# vario.net
KiCad netlist of a schematic drawn in EAGLE
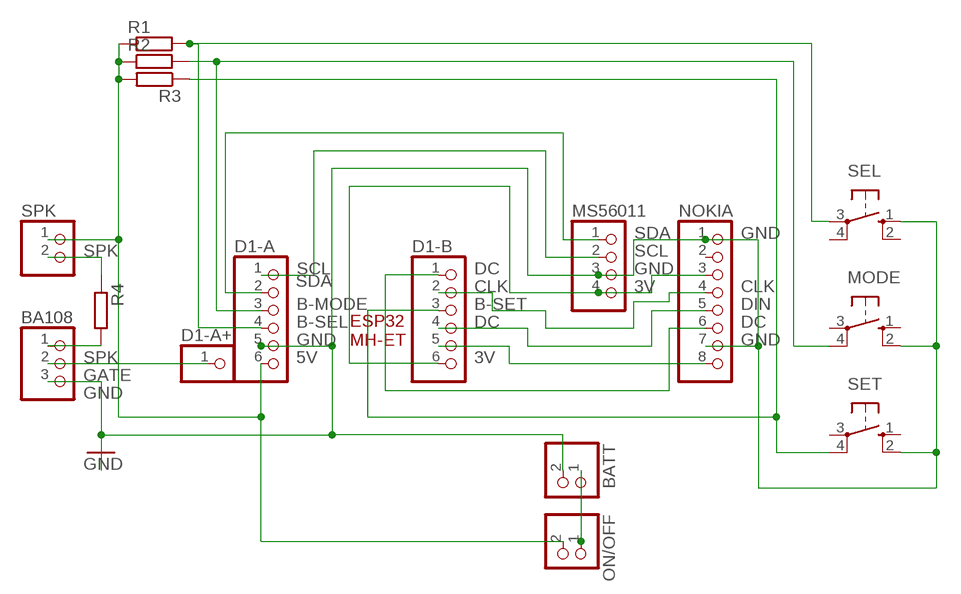
[diagram p0: schematic, sheet 1]

(export (version "E")
  (design (tool "Eeschema 10.0.6"))
  (components
    (comp (ref "BA108")
      (value "PINHD-1X3")
      (footprint "eagle-import:1X03")
      (libsource (lib "eagle-import") (part "PINHD-1X3"))
    )
    (comp (ref "BATT")
      (value "PINHD-1X2")
      (footprint "eagle-import:1X02")
      (libsource (lib "eagle-import") (part "PINHD-1X2"))
    )
    (comp (ref "D1-A")
      (value "PINHD-1X6")
      (footprint "eagle-import:1X06")
      (libsource (lib "eagle-import") (part "PINHD-1X6"))
    )
    (comp (ref "D1-A+")
      (value "PINHD-1X1")
      (footprint "eagle-import:1X01")
      (libsource (lib "eagle-import") (part "PINHD-1X1"))
    )
    (comp (ref "D1-B")
      (value "PINHD-1X6")
      (footprint "eagle-import:1X06")
      (libsource (lib "eagle-import") (part "PINHD-1X6"))
    )
    (comp (ref "MODE")
      (value "10-XX")
      (footprint "eagle-import:B3F-10XX")
      (fields (field (name "MPN") "B3F-1000"))
      (libsource (lib "eagle-import") (part "10-XX"))
    )
    (comp (ref "MS56011")
      (value "PINHD-1X4")
      (footprint "eagle-import:1X04")
      (libsource (lib "eagle-import") (part "PINHD-1X4"))
    )
    (comp (ref "NOKIA")
      (value "PINHD-1X8")
      (footprint "eagle-import:1X08")
      (libsource (lib "eagle-import") (part "PINHD-1X8"))
    )
    (comp (ref "ON/OFF")
      (value "PINHD-1X2")
      (footprint "eagle-import:1X02")
      (libsource (lib "eagle-import") (part "PINHD-1X2"))
    )
    (comp (ref "R1")
      (value "R-EU_0207/10")
      (footprint "eagle-import:0207_10")
      (libsource (lib "eagle-import") (part "R-EU_0207/10"))
    )
    (comp (ref "R2")
      (value "R-EU_0207/10")
      (footprint "eagle-import:0207_10")
      (libsource (lib "eagle-import") (part "R-EU_0207/10"))
    )
    (comp (ref "R3")
      (value "R-EU_0207/10")
      (footprint "eagle-import:0207_10")
      (libsource (lib "eagle-import") (part "R-EU_0207/10"))
    )
    (comp (ref "R4")
      (value "R-EU_0207/10")
      (footprint "eagle-import:0207_10")
      (libsource (lib "eagle-import") (part "R-EU_0207/10"))
    )
    (comp (ref "SEL")
      (value "10-XX")
      (footprint "eagle-import:B3F-10XX")
      (fields (field (name "MPN") "B3F-1000"))
      (libsource (lib "eagle-import") (part "10-XX"))
    )
    (comp (ref "SET")
      (value "10-XX")
      (footprint "eagle-import:B3F-10XX")
      (fields (field (name "MPN") "B3F-1000"))
      (libsource (lib "eagle-import") (part "10-XX"))
    )
    (comp (ref "SPK")
      (value "PINHD-1X2")
      (footprint "eagle-import:1X02")
      (libsource (lib "eagle-import") (part "PINHD-1X2"))
    )
  )
  (nets
    (net (code "1") (name "/3V") (class "Default")
      (node (ref "D1-B") (pin "6") (pinfunction "6_6") (pintype "passive"))
      (node (ref "MS56011") (pin "4") (pinfunction "4_4") (pintype "passive"))
      (node (ref "NOKIA") (pin "3") (pinfunction "3_3") (pintype "passive"))
    )
    (net (code "2") (name "/5V") (class "Default")
      (node (ref "D1-A") (pin "6") (pinfunction "6_6") (pintype "passive"))
      (node (ref "ON/OFF") (pin "2") (pinfunction "2_2") (pintype "passive"))
      (node (ref "R1") (pin "1") (pinfunction "1_1") (pintype "passive"))
      (node (ref "R2") (pin "1") (pinfunction "1_1") (pintype "passive"))
      (node (ref "R3") (pin "2") (pinfunction "2_2") (pintype "passive"))
      (node (ref "SPK") (pin "1") (pinfunction "1_1") (pintype "passive"))
    )
    (net (code "3") (name "/B-MODE") (class "Default")
      (node (ref "D1-A") (pin "3") (pinfunction "3_3") (pintype "passive"))
      (node (ref "MODE") (pin "4") (pinfunction "P1_4") (pintype "passive"))
      (node (ref "R2") (pin "2") (pinfunction "2_2") (pintype "passive"))
    )
    (net (code "4") (name "/B-SEL") (class "Default")
      (node (ref "D1-A") (pin "4") (pinfunction "4_4") (pintype "passive"))
      (node (ref "R1") (pin "2") (pinfunction "2_2") (pintype "passive"))
      (node (ref "SEL") (pin "3") (pinfunction "P_3") (pintype "passive"))
    )
    (net (code "5") (name "/B-SET") (class "Default")
      (node (ref "D1-B") (pin "3") (pinfunction "3_3") (pintype "passive"))
      (node (ref "R3") (pin "1") (pinfunction "1_1") (pintype "passive"))
      (node (ref "SET") (pin "4") (pinfunction "P1_4") (pintype "passive"))
    )
    (net (code "6") (name "/CLK") (class "Default")
      (node (ref "D1-B") (pin "2") (pinfunction "2_2") (pintype "passive"))
      (node (ref "NOKIA") (pin "4") (pinfunction "4_4") (pintype "passive"))
    )
    (net (code "7") (name "/DC") (class "Default")
      (node (ref "D1-B") (pin "1") (pinfunction "1_1") (pintype "passive"))
      (node (ref "NOKIA") (pin "6") (pinfunction "6_6") (pintype "passive"))
    )
    (net (code "8") (name "/DIN") (class "Default")
      (node (ref "D1-B") (pin "4") (pinfunction "4_4") (pintype "passive"))
      (node (ref "NOKIA") (pin "5") (pinfunction "5_5") (pintype "passive"))
    )
    (net (code "9") (name "/GATE") (class "Default")
      (node (ref "BA108") (pin "2") (pinfunction "2_2") (pintype "passive"))
      (node (ref "D1-A+") (pin "1") (pinfunction "1_1") (pintype "passive"))
    )
    (net (code "10") (name "/SCL") (class "Default")
      (node (ref "D1-A") (pin "1") (pinfunction "1_1") (pintype "passive"))
      (node (ref "MS56011") (pin "2") (pinfunction "2_2") (pintype "passive"))
    )
    (net (code "11") (name "/SDA") (class "Default")
      (node (ref "D1-A") (pin "2") (pinfunction "2_2") (pintype "passive"))
      (node (ref "MS56011") (pin "1") (pinfunction "1_1") (pintype "passive"))
    )
    (net (code "12") (name "/SPK") (class "Default")
      (node (ref "BA108") (pin "1") (pinfunction "1_1") (pintype "passive"))
      (node (ref "R4") (pin "2") (pinfunction "2_2") (pintype "passive"))
    )
    (net (code "13") (name "GND") (class "Default")
      (node (ref "BA108") (pin "3") (pinfunction "3_3") (pintype "passive"))
      (node (ref "BATT") (pin "2") (pinfunction "2_2") (pintype "passive"))
      (node (ref "D1-A") (pin "5") (pinfunction "5_5") (pintype "passive"))
      (node (ref "MODE") (pin "2") (pinfunction "S1_2") (pintype "passive"))
      (node (ref "MS56011") (pin "3") (pinfunction "3_3") (pintype "passive"))
      (node (ref "NOKIA") (pin "1") (pinfunction "1_1") (pintype "passive"))
      (node (ref "NOKIA") (pin "7") (pinfunction "7_7") (pintype "passive"))
      (node (ref "SEL") (pin "1") (pinfunction "S_1") (pintype "passive"))
      (node (ref "SET") (pin "2") (pinfunction "S1_2") (pintype "passive"))
    )
    (net (code "14") (name "Net-(BATT-Pad1)") (class "Default")
      (node (ref "BATT") (pin "1") (pinfunction "1_1") (pintype "passive"))
      (node (ref "ON/OFF") (pin "1") (pinfunction "1_1") (pintype "passive"))
    )
    (net (code "15") (name "Net-(D1-B-Pad5)") (class "Default")
      (node (ref "D1-B") (pin "5") (pinfunction "5_5") (pintype "passive"))
      (node (ref "NOKIA") (pin "8") (pinfunction "8_8") (pintype "passive"))
    )
    (net (code "16") (name "Net-(R4-Pad1)") (class "Default")
      (node (ref "R4") (pin "1") (pinfunction "1_1") (pintype "passive"))
      (node (ref "SPK") (pin "2") (pinfunction "2_2") (pintype "passive"))
    )
    (net (code "17") (name "unconnected-(MODE-P-Pad3)") (class "Default")
      (node (ref "MODE") (pin "3") (pinfunction "P_3") (pintype "passive"))
    )
    (net (code "18") (name "unconnected-(MODE-S-Pad1)") (class "Default")
      (node (ref "MODE") (pin "1") (pinfunction "S_1") (pintype "passive"))
    )
    (net (code "19") (name "unconnected-(NOKIA-Pad2)") (class "Default")
      (node (ref "NOKIA") (pin "2") (pinfunction "2_2") (pintype "passive"))
    )
    (net (code "20") (name "unconnected-(SEL-P1-Pad4)") (class "Default")
      (node (ref "SEL") (pin "4") (pinfunction "P1_4") (pintype "passive"))
    )
    (net (code "21") (name "unconnected-(SEL-S1-Pad2)") (class "Default")
      (node (ref "SEL") (pin "2") (pinfunction "S1_2") (pintype "passive"))
    )
    (net (code "22") (name "unconnected-(SET-P-Pad3)") (class "Default")
      (node (ref "SET") (pin "3") (pinfunction "P_3") (pintype "passive"))
    )
    (net (code "23") (name "unconnected-(SET-S-Pad1)") (class "Default")
      (node (ref "SET") (pin "1") (pinfunction "S_1") (pintype "passive"))
    )
  )
)
